# EsayEDA_schematic_for_PrismFX.net
KiCad netlist of a schematic drawn in EasyEDA
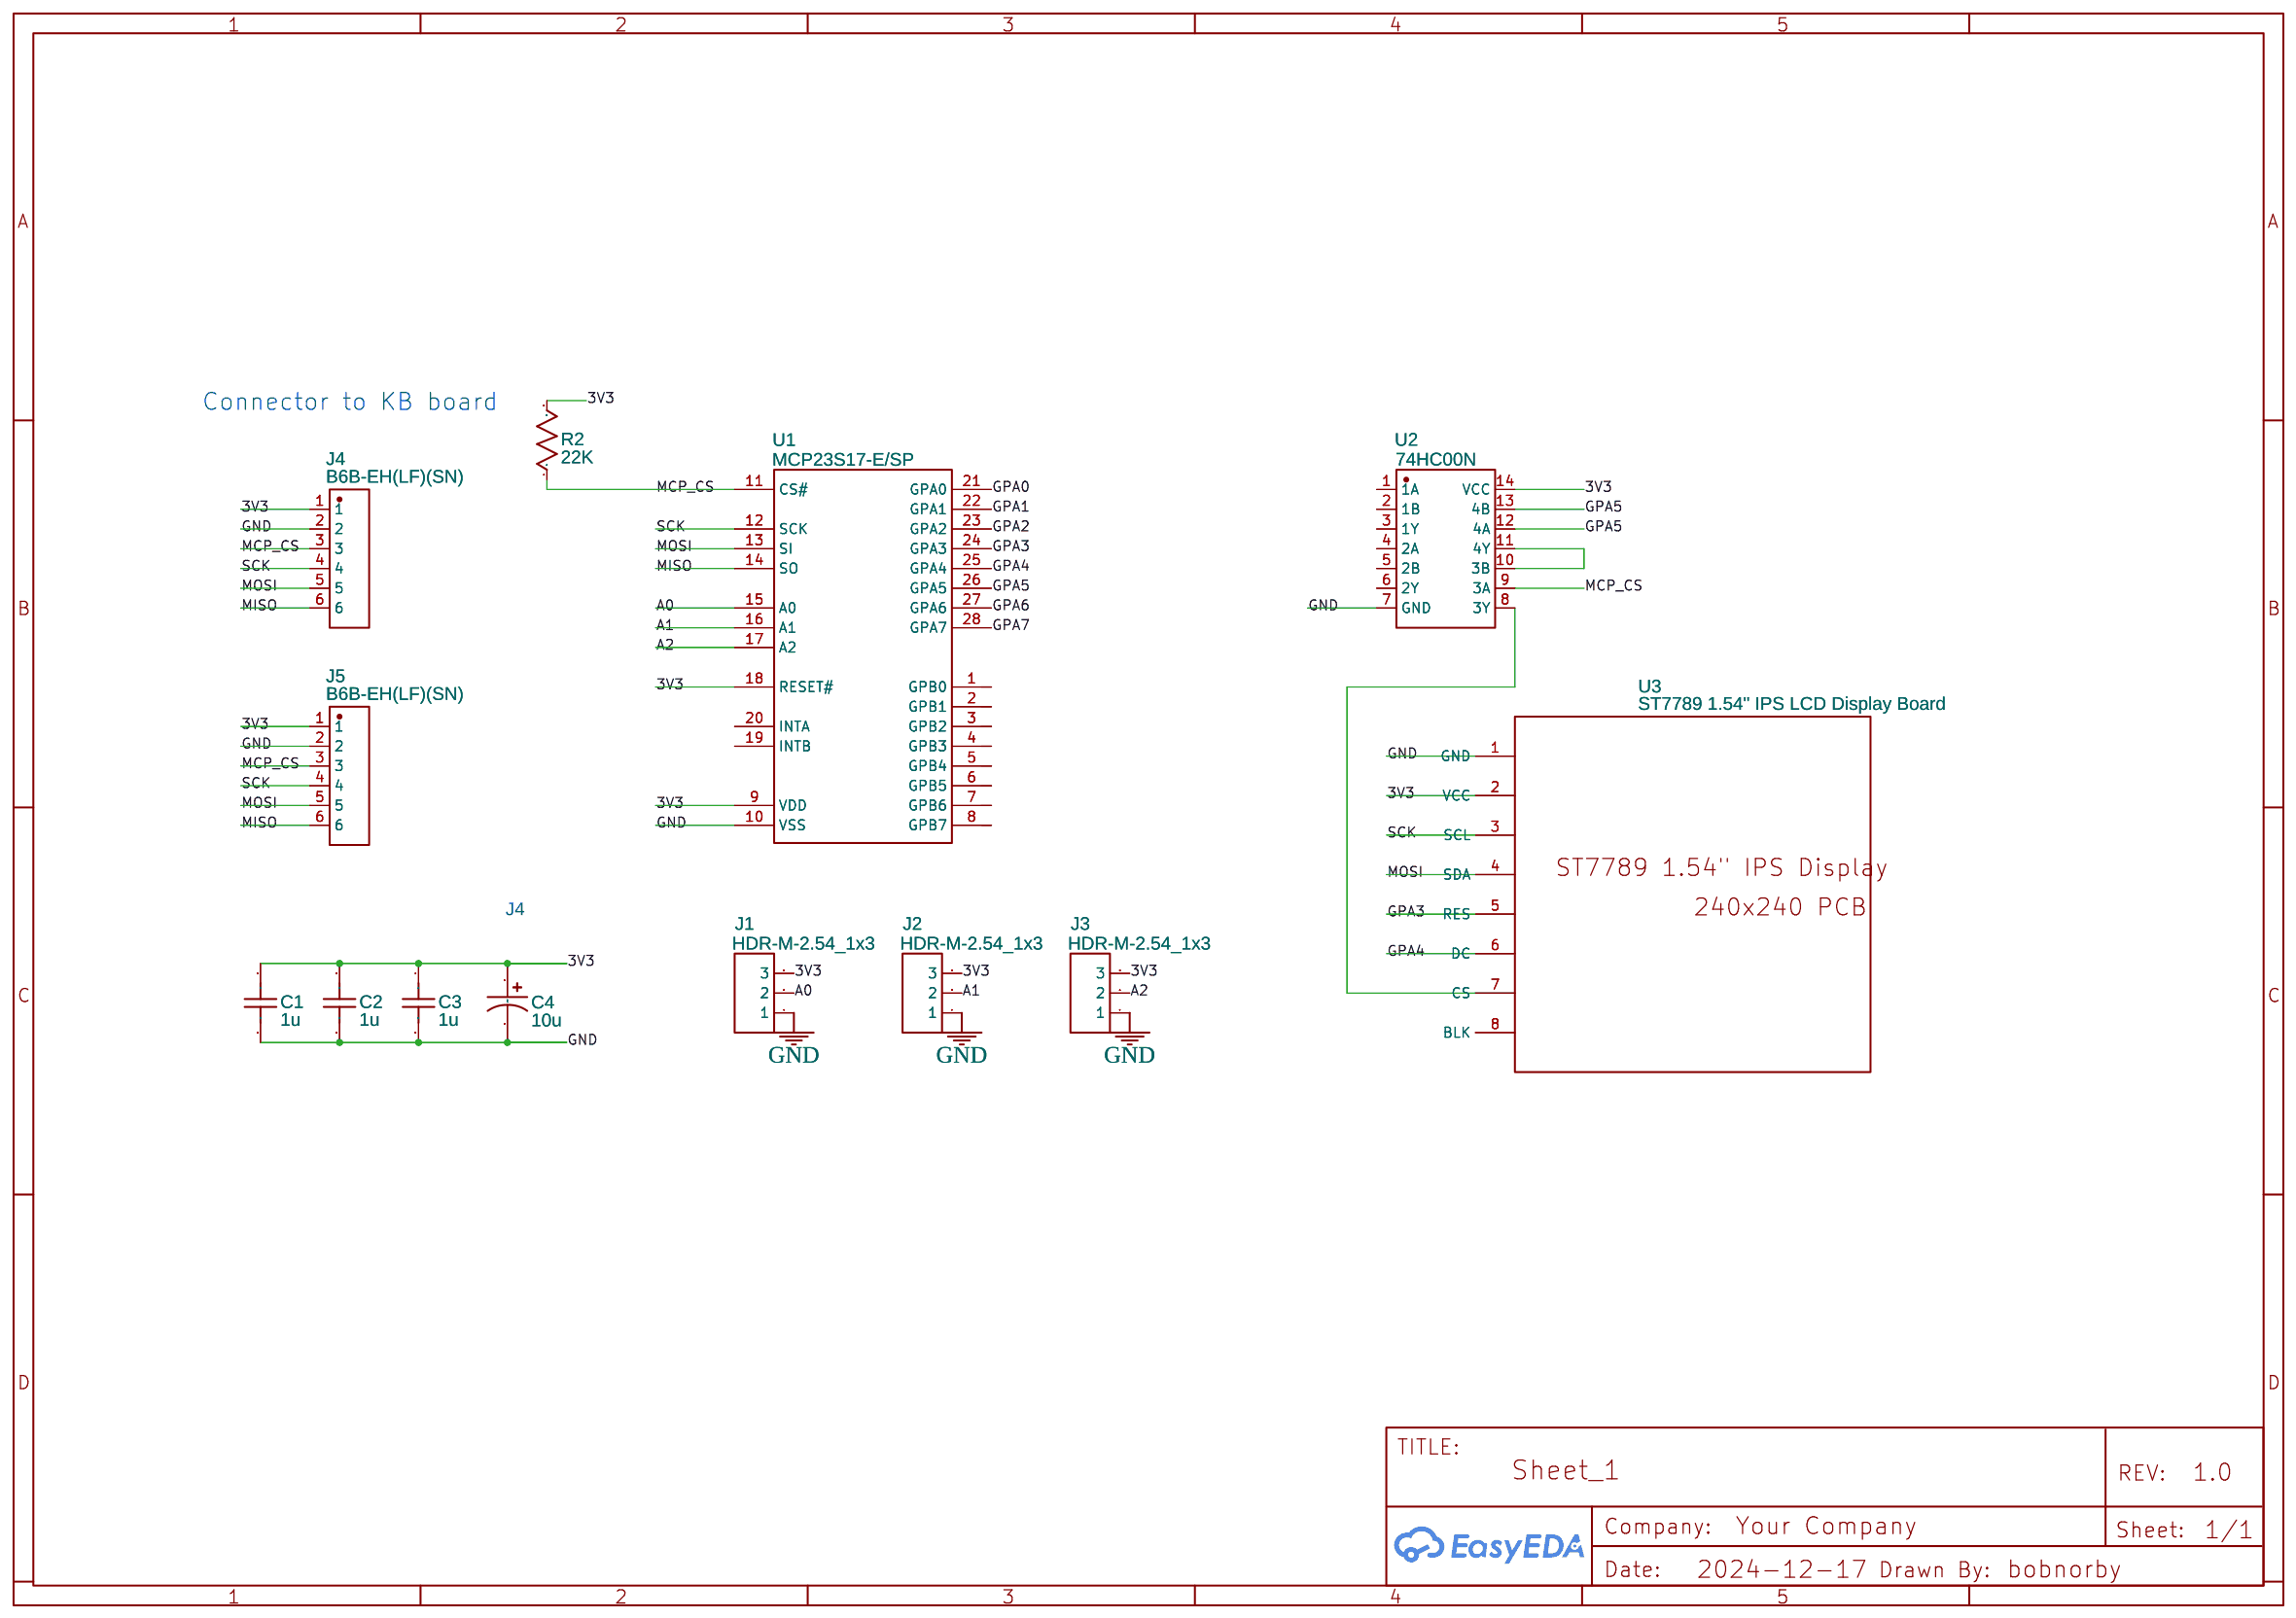
[diagram p0: schematic sheet]

(export (version "E")
  (design (tool "Eeschema 10.0.6"))
  (components
    (comp (ref "C1") (value "1u") (libsource (lib "") (part "C_RAD-0.1_US")))
    (comp (ref "C2") (value "1u") (libsource (lib "") (part "C_RAD-0.1_US")))
    (comp (ref "C3") (value "1u") (libsource (lib "") (part "C_RAD-0.1_US")))
    (comp (ref "C4") (value "10u") (libsource (lib "") (part "CE_TH_D5.0×F2.0_US")))
    (comp (ref "J1") (value "HDR-M-2.54_1x3") (libsource (lib "") (part "HDR-M-2.54_1x3")))
    (comp (ref "J2") (value "HDR-M-2.54_1x3") (libsource (lib "") (part "HDR-M-2.54_1x3")))
    (comp (ref "J3") (value "HDR-M-2.54_1x3") (libsource (lib "") (part "HDR-M-2.54_1x3")))
    (comp (ref "J4")
      (value "B6B-EH(LF)(SN)")
      (fields (field (name "Manufacturer") "JST"))
      (libsource (lib "") (part "B6B-EH(LF)(SN)"))
    )
    (comp (ref "J5")
      (value "B6B-EH(LF)(SN)")
      (fields (field (name "Manufacturer") "JST"))
      (libsource (lib "") (part "B6B-EH(LF)(SN)"))
    )
    (comp (ref "R2") (value "22K") (libsource (lib "") (part "R_AXIAL-0.3_US")))
    (comp (ref "U1")
      (value "MCP23S17-E/SP")
      (fields (field (name "Manufacturer") "MICROCHIP(美国微芯)"))
      (libsource (lib "") (part "MCP23S17-E/SP"))
    )
    (comp (ref "U2")
      (value "74HC00N")
      (fields (field (name "Manufacturer") "HGSEMI(华冠)"))
      (libsource (lib "") (part "74HC00N"))
    )
    (comp (ref "U3")
      (value "ST7789 1.54\" IPS LCD Display Board")
      (libsource (lib "") (part "ST7789 1.54{dblquote} IPS LCD Display Board"))
    )
  )
  (nets
    (net (code "1") (name "/3V3") (class "Default")
      (node (ref "C1") (pin "1") (pinfunction "1_1") (pintype "unspecified"))
      (node (ref "C2") (pin "1") (pinfunction "1_1") (pintype "unspecified"))
      (node (ref "C3") (pin "1") (pinfunction "1_1") (pintype "unspecified"))
      (node (ref "C4") (pin "1") (pinfunction "1_1") (pintype "unspecified"))
      (node (ref "J1") (pin "3") (pinfunction "3_3") (pintype "input"))
      (node (ref "J2") (pin "3") (pinfunction "3_3") (pintype "input"))
      (node (ref "J3") (pin "3") (pinfunction "3_3") (pintype "input"))
      (node (ref "J4") (pin "1") (pinfunction "1_1") (pintype "unspecified"))
      (node (ref "J5") (pin "1") (pinfunction "1_1") (pintype "unspecified"))
      (node (ref "R2") (pin "2") (pinfunction "2_2") (pintype "unspecified"))
      (node (ref "U1") (pin "18") (pinfunction "RESET#_18") (pintype "unspecified"))
      (node (ref "U1") (pin "9") (pinfunction "VDD_9") (pintype "passive"))
      (node (ref "U2") (pin "14") (pinfunction "VCC_14") (pintype "unspecified"))
      (node (ref "U3") (pin "2") (pinfunction "VCC_2") (pintype "unspecified"))
    )
    (net (code "2") (name "/A0") (class "Default")
      (node (ref "J1") (pin "2") (pinfunction "2_2") (pintype "input"))
      (node (ref "U1") (pin "15") (pinfunction "A0_15") (pintype "unspecified"))
    )
    (net (code "3") (name "/A1") (class "Default")
      (node (ref "J2") (pin "2") (pinfunction "2_2") (pintype "input"))
      (node (ref "U1") (pin "16") (pinfunction "A1_16") (pintype "unspecified"))
    )
    (net (code "4") (name "/A2") (class "Default")
      (node (ref "J3") (pin "2") (pinfunction "2_2") (pintype "input"))
      (node (ref "U1") (pin "17") (pinfunction "A2_17") (pintype "unspecified"))
    )
    (net (code "5") (name "/GPA0") (class "Default")
      (node (ref "U1") (pin "21") (pinfunction "GPA0_21") (pintype "bidirectional"))
    )
    (net (code "6") (name "/GPA1") (class "Default")
      (node (ref "U1") (pin "22") (pinfunction "GPA1_22") (pintype "bidirectional"))
    )
    (net (code "7") (name "/GPA2") (class "Default")
      (node (ref "U1") (pin "23") (pinfunction "GPA2_23") (pintype "bidirectional"))
    )
    (net (code "8") (name "/GPA3") (class "Default")
      (node (ref "U1") (pin "24") (pinfunction "GPA3_24") (pintype "bidirectional"))
      (node (ref "U3") (pin "5") (pinfunction "RES_5") (pintype "unspecified"))
    )
    (net (code "9") (name "/GPA4") (class "Default")
      (node (ref "U1") (pin "25") (pinfunction "GPA4_25") (pintype "bidirectional"))
      (node (ref "U3") (pin "6") (pinfunction "DC_6") (pintype "unspecified"))
    )
    (net (code "10") (name "/GPA5") (class "Default")
      (node (ref "U1") (pin "26") (pinfunction "GPA5_26") (pintype "bidirectional"))
      (node (ref "U2") (pin "12") (pinfunction "4A_12") (pintype "unspecified"))
      (node (ref "U2") (pin "13") (pinfunction "4B_13") (pintype "unspecified"))
    )
    (net (code "11") (name "/GPA6") (class "Default")
      (node (ref "U1") (pin "27") (pinfunction "GPA6_27") (pintype "bidirectional"))
    )
    (net (code "12") (name "/GPA7") (class "Default")
      (node (ref "U1") (pin "28") (pinfunction "GPA7_28") (pintype "bidirectional"))
    )
    (net (code "13") (name "/MCP_CS") (class "Default")
      (node (ref "J4") (pin "3") (pinfunction "3_3") (pintype "unspecified"))
      (node (ref "J5") (pin "3") (pinfunction "3_3") (pintype "unspecified"))
      (node (ref "R2") (pin "1") (pinfunction "1_1") (pintype "unspecified"))
      (node (ref "U1") (pin "11") (pinfunction "CS#_11") (pintype "unspecified"))
      (node (ref "U2") (pin "9") (pinfunction "3A_9") (pintype "unspecified"))
    )
    (net (code "14") (name "/MISO") (class "Default")
      (node (ref "J4") (pin "6") (pinfunction "6_6") (pintype "unspecified"))
      (node (ref "J5") (pin "6") (pinfunction "6_6") (pintype "unspecified"))
      (node (ref "U1") (pin "14") (pinfunction "SO_14") (pintype "unspecified"))
    )
    (net (code "15") (name "/MOSI") (class "Default")
      (node (ref "J4") (pin "5") (pinfunction "5_5") (pintype "unspecified"))
      (node (ref "J5") (pin "5") (pinfunction "5_5") (pintype "unspecified"))
      (node (ref "U1") (pin "13") (pinfunction "SI_13") (pintype "unspecified"))
      (node (ref "U3") (pin "4") (pinfunction "SDA_4") (pintype "unspecified"))
    )
    (net (code "16") (name "/SCK") (class "Default")
      (node (ref "J4") (pin "4") (pinfunction "4_4") (pintype "unspecified"))
      (node (ref "J5") (pin "4") (pinfunction "4_4") (pintype "unspecified"))
      (node (ref "U1") (pin "12") (pinfunction "SCK_12") (pintype "unspecified"))
      (node (ref "U3") (pin "3") (pinfunction "SCL_3") (pintype "unspecified"))
    )
    (net (code "17") (name "GND") (class "Default")
      (node (ref "C1") (pin "2") (pinfunction "2_2") (pintype "unspecified"))
      (node (ref "C2") (pin "2") (pinfunction "2_2") (pintype "unspecified"))
      (node (ref "C3") (pin "2") (pinfunction "2_2") (pintype "unspecified"))
      (node (ref "C4") (pin "2") (pinfunction "2_2") (pintype "unspecified"))
      (node (ref "J1") (pin "1") (pinfunction "1_1") (pintype "input"))
      (node (ref "J2") (pin "1") (pinfunction "1_1") (pintype "input"))
      (node (ref "J3") (pin "1") (pinfunction "1_1") (pintype "input"))
      (node (ref "J4") (pin "2") (pinfunction "2_2") (pintype "unspecified"))
      (node (ref "J5") (pin "2") (pinfunction "2_2") (pintype "unspecified"))
      (node (ref "U1") (pin "10") (pinfunction "VSS_10") (pintype "passive"))
      (node (ref "U2") (pin "7") (pinfunction "GND_7") (pintype "unspecified"))
      (node (ref "U3") (pin "1") (pinfunction "GND_1") (pintype "unspecified"))
    )
    (net (code "18") (name "Net-(U2-3B)") (class "Default")
      (node (ref "U2") (pin "10") (pinfunction "3B_10") (pintype "unspecified"))
      (node (ref "U2") (pin "11") (pinfunction "4Y_11") (pintype "unspecified"))
    )
    (net (code "19") (name "Net-(U2-3Y)") (class "Default")
      (node (ref "U2") (pin "8") (pinfunction "3Y_8") (pintype "unspecified"))
      (node (ref "U3") (pin "7") (pinfunction "CS_7") (pintype "unspecified"))
    )
    (net (code "20") (name "unconnected-(U1-GPB0-Pad1)") (class "Default")
      (node (ref "U1") (pin "1") (pinfunction "GPB0_1") (pintype "bidirectional"))
    )
    (net (code "21") (name "unconnected-(U1-GPB1-Pad2)") (class "Default")
      (node (ref "U1") (pin "2") (pinfunction "GPB1_2") (pintype "bidirectional"))
    )
    (net (code "22") (name "unconnected-(U1-GPB2-Pad3)") (class "Default")
      (node (ref "U1") (pin "3") (pinfunction "GPB2_3") (pintype "bidirectional"))
    )
    (net (code "23") (name "unconnected-(U1-GPB3-Pad4)") (class "Default")
      (node (ref "U1") (pin "4") (pinfunction "GPB3_4") (pintype "bidirectional"))
    )
    (net (code "24") (name "unconnected-(U1-GPB4-Pad5)") (class "Default")
      (node (ref "U1") (pin "5") (pinfunction "GPB4_5") (pintype "bidirectional"))
    )
    (net (code "25") (name "unconnected-(U1-GPB5-Pad6)") (class "Default")
      (node (ref "U1") (pin "6") (pinfunction "GPB5_6") (pintype "bidirectional"))
    )
    (net (code "26") (name "unconnected-(U1-GPB6-Pad7)") (class "Default")
      (node (ref "U1") (pin "7") (pinfunction "GPB6_7") (pintype "bidirectional"))
    )
    (net (code "27") (name "unconnected-(U1-GPB7-Pad8)") (class "Default")
      (node (ref "U1") (pin "8") (pinfunction "GPB7_8") (pintype "bidirectional"))
    )
    (net (code "28") (name "unconnected-(U1-INTA-Pad20)") (class "Default")
      (node (ref "U1") (pin "20") (pinfunction "INTA_20") (pintype "unspecified"))
    )
    (net (code "29") (name "unconnected-(U1-INTB-Pad19)") (class "Default")
      (node (ref "U1") (pin "19") (pinfunction "INTB_19") (pintype "unspecified"))
    )
    (net (code "30") (name "unconnected-(U2-1A-Pad1)") (class "Default")
      (node (ref "U2") (pin "1") (pinfunction "1A_1") (pintype "unspecified"))
    )
    (net (code "31") (name "unconnected-(U2-1B-Pad2)") (class "Default")
      (node (ref "U2") (pin "2") (pinfunction "1B_2") (pintype "unspecified"))
    )
    (net (code "32") (name "unconnected-(U2-1Y-Pad3)") (class "Default")
      (node (ref "U2") (pin "3") (pinfunction "1Y_3") (pintype "unspecified"))
    )
    (net (code "33") (name "unconnected-(U2-2A-Pad4)") (class "Default")
      (node (ref "U2") (pin "4") (pinfunction "2A_4") (pintype "unspecified"))
    )
    (net (code "34") (name "unconnected-(U2-2B-Pad5)") (class "Default")
      (node (ref "U2") (pin "5") (pinfunction "2B_5") (pintype "unspecified"))
    )
    (net (code "35") (name "unconnected-(U2-2Y-Pad6)") (class "Default")
      (node (ref "U2") (pin "6") (pinfunction "2Y_6") (pintype "unspecified"))
    )
    (net (code "36") (name "unconnected-(U3-BLK-Pad8)") (class "Default")
      (node (ref "U3") (pin "8") (pinfunction "BLK_8") (pintype "unspecified"))
    )
  )
)
